# coffee_maker.net
KiCad netlist of a schematic drawn in EAGLE
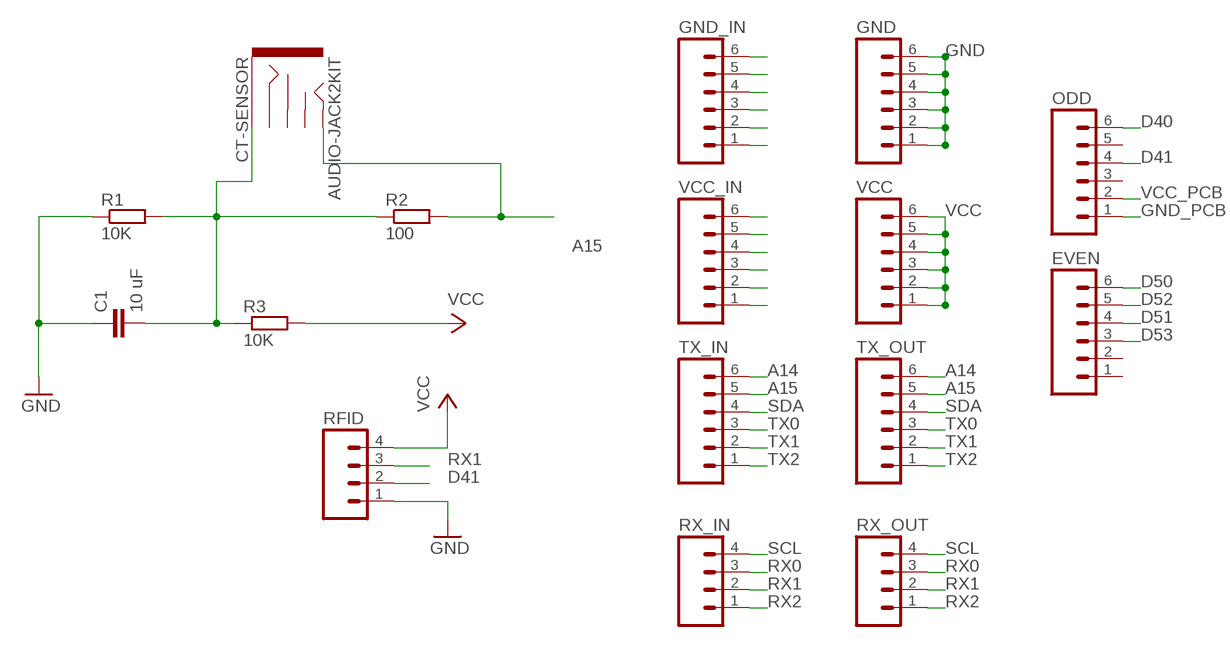
[diagram p0: schematic, sheet 1]

(export (version "E")
  (design (tool "Eeschema 10.0.6"))
  (components
    (comp (ref "C1")
      (value "10 uF")
      (footprint "eagle-import:C1206")
      (libsource (lib "eagle-import") (part "C-EUC1206"))
    )
    (comp (ref "CT-SENSOR")
      (value "AUDIO-JACK2KIT")
      (footprint "eagle-import:AUDIO-JACK-KIT")
      (libsource (lib "eagle-import") (part "AUDIO-JACK2KIT"))
    )
    (comp (ref "EVEN")
      (value "M06SIP")
      (footprint "eagle-import:1X06")
      (libsource (lib "eagle-import") (part "M06SIP"))
    )
    (comp (ref "GND")
      (value "M06SIP")
      (footprint "eagle-import:1X06")
      (libsource (lib "eagle-import") (part "M06SIP"))
    )
    (comp (ref "GND_IN")
      (value "M06SIP")
      (footprint "eagle-import:1X06")
      (libsource (lib "eagle-import") (part "M06SIP"))
    )
    (comp (ref "ODD")
      (value "M06SIP")
      (footprint "eagle-import:1X06")
      (libsource (lib "eagle-import") (part "M06SIP"))
    )
    (comp (ref "R1")
      (value "10K")
      (footprint "eagle-import:M1206")
      (libsource (lib "eagle-import") (part "R-EU_M1206"))
    )
    (comp (ref "R2")
      (value "100")
      (footprint "eagle-import:M1206")
      (libsource (lib "eagle-import") (part "R-EU_M1206"))
    )
    (comp (ref "R3")
      (value "10K")
      (footprint "eagle-import:M1206")
      (libsource (lib "eagle-import") (part "R-EU_M1206"))
    )
    (comp (ref "RFID")
      (value "M04SMD2")
      (footprint "eagle-import:1X04-1MM-RA")
      (libsource (lib "eagle-import") (part "M04SMD2"))
    )
    (comp (ref "RX_IN")
      (value "M04PTH")
      (footprint "eagle-import:1X04")
      (libsource (lib "eagle-import") (part "M04PTH"))
    )
    (comp (ref "RX_OUT")
      (value "M04PTH")
      (footprint "eagle-import:1X04")
      (libsource (lib "eagle-import") (part "M04PTH"))
    )
    (comp (ref "TX_IN")
      (value "M06SIP")
      (footprint "eagle-import:1X06")
      (libsource (lib "eagle-import") (part "M06SIP"))
    )
    (comp (ref "TX_OUT")
      (value "M06SIP")
      (footprint "eagle-import:1X06")
      (libsource (lib "eagle-import") (part "M06SIP"))
    )
    (comp (ref "VCC")
      (value "M06SIP")
      (footprint "eagle-import:1X06")
      (libsource (lib "eagle-import") (part "M06SIP"))
    )
    (comp (ref "VCC_IN")
      (value "M06SIP")
      (footprint "eagle-import:1X06")
      (libsource (lib "eagle-import") (part "M06SIP"))
    )
  )
  (nets
    (net (code "1") (name "/A14") (class "Default")
      (node (ref "TX_IN") (pin "6") (pinfunction "6_6") (pintype "passive"))
      (node (ref "TX_OUT") (pin "6") (pinfunction "6_6") (pintype "passive"))
    )
    (net (code "2") (name "/A15") (class "Default")
      (node (ref "CT-SENSOR") (pin "TIP") (pinfunction "TIP_TIP") (pintype "bidirectional"))
      (node (ref "R2") (pin "2") (pinfunction "2_2") (pintype "passive"))
      (node (ref "TX_IN") (pin "5") (pinfunction "5_5") (pintype "passive"))
      (node (ref "TX_OUT") (pin "5") (pinfunction "5_5") (pintype "passive"))
    )
    (net (code "3") (name "/D40") (class "Default")
      (node (ref "ODD") (pin "6") (pinfunction "6_6") (pintype "passive"))
    )
    (net (code "4") (name "/D41") (class "Default")
      (node (ref "ODD") (pin "4") (pinfunction "4_4") (pintype "passive"))
      (node (ref "RFID") (pin "2") (pinfunction "2_2") (pintype "passive"))
    )
    (net (code "5") (name "/D50") (class "Default")
      (node (ref "EVEN") (pin "6") (pinfunction "6_6") (pintype "passive"))
    )
    (net (code "6") (name "/D51") (class "Default")
      (node (ref "EVEN") (pin "4") (pinfunction "4_4") (pintype "passive"))
    )
    (net (code "7") (name "/D52") (class "Default")
      (node (ref "EVEN") (pin "5") (pinfunction "5_5") (pintype "passive"))
    )
    (net (code "8") (name "/D53") (class "Default")
      (node (ref "EVEN") (pin "3") (pinfunction "3_3") (pintype "passive"))
    )
    (net (code "9") (name "/GND_PCB") (class "Default")
      (node (ref "ODD") (pin "1") (pinfunction "1_1") (pintype "passive"))
    )
    (net (code "10") (name "/RX0") (class "Default")
      (node (ref "RX_IN") (pin "3") (pinfunction "3_3") (pintype "passive"))
      (node (ref "RX_OUT") (pin "3") (pinfunction "3_3") (pintype "passive"))
    )
    (net (code "11") (name "/RX1") (class "Default")
      (node (ref "RFID") (pin "3") (pinfunction "3_3") (pintype "passive"))
      (node (ref "RX_IN") (pin "2") (pinfunction "2_2") (pintype "passive"))
      (node (ref "RX_OUT") (pin "2") (pinfunction "2_2") (pintype "passive"))
    )
    (net (code "12") (name "/RX2") (class "Default")
      (node (ref "RX_IN") (pin "1") (pinfunction "1_1") (pintype "passive"))
      (node (ref "RX_OUT") (pin "1") (pinfunction "1_1") (pintype "passive"))
    )
    (net (code "13") (name "/SCL") (class "Default")
      (node (ref "RX_IN") (pin "4") (pinfunction "4_4") (pintype "passive"))
      (node (ref "RX_OUT") (pin "4") (pinfunction "4_4") (pintype "passive"))
    )
    (net (code "14") (name "/SDA") (class "Default")
      (node (ref "TX_IN") (pin "4") (pinfunction "4_4") (pintype "passive"))
      (node (ref "TX_OUT") (pin "4") (pinfunction "4_4") (pintype "passive"))
    )
    (net (code "15") (name "/TX0") (class "Default")
      (node (ref "TX_IN") (pin "3") (pinfunction "3_3") (pintype "passive"))
      (node (ref "TX_OUT") (pin "3") (pinfunction "3_3") (pintype "passive"))
    )
    (net (code "16") (name "/TX1") (class "Default")
      (node (ref "TX_IN") (pin "2") (pinfunction "2_2") (pintype "passive"))
      (node (ref "TX_OUT") (pin "2") (pinfunction "2_2") (pintype "passive"))
    )
    (net (code "17") (name "/TX2") (class "Default")
      (node (ref "TX_IN") (pin "1") (pinfunction "1_1") (pintype "passive"))
      (node (ref "TX_OUT") (pin "1") (pinfunction "1_1") (pintype "passive"))
    )
    (net (code "18") (name "/VCC_PCB") (class "Default")
      (node (ref "ODD") (pin "2") (pinfunction "2_2") (pintype "passive"))
    )
    (net (code "19") (name "GND") (class "Default")
      (node (ref "C1") (pin "1") (pinfunction "1_1") (pintype "passive"))
      (node (ref "GND") (pin "1") (pinfunction "1_1") (pintype "passive"))
      (node (ref "GND") (pin "2") (pinfunction "2_2") (pintype "passive"))
      (node (ref "GND") (pin "3") (pinfunction "3_3") (pintype "passive"))
      (node (ref "GND") (pin "4") (pinfunction "4_4") (pintype "passive"))
      (node (ref "GND") (pin "5") (pinfunction "5_5") (pintype "passive"))
      (node (ref "GND") (pin "6") (pinfunction "6_6") (pintype "passive"))
      (node (ref "GND_IN") (pin "6") (pinfunction "6_6") (pintype "passive"))
      (node (ref "R1") (pin "1") (pinfunction "1_1") (pintype "passive"))
      (node (ref "RFID") (pin "1") (pinfunction "1_1") (pintype "passive"))
    )
    (net (code "20") (name "Net-(C1-Pad2)") (class "Default")
      (node (ref "C1") (pin "2") (pinfunction "2_2") (pintype "passive"))
      (node (ref "CT-SENSOR") (pin "SLEEVE") (pinfunction "SLEEVE_SLEEVE") (pintype "bidirectional"))
      (node (ref "R1") (pin "2") (pinfunction "2_2") (pintype "passive"))
      (node (ref "R2") (pin "1") (pinfunction "1_1") (pintype "passive"))
      (node (ref "R3") (pin "1") (pinfunction "1_1") (pintype "passive"))
    )
    (net (code "21") (name "VCC") (class "Default")
      (node (ref "R3") (pin "2") (pinfunction "2_2") (pintype "passive"))
      (node (ref "RFID") (pin "4") (pinfunction "4_4") (pintype "passive"))
      (node (ref "VCC") (pin "1") (pinfunction "1_1") (pintype "passive"))
      (node (ref "VCC") (pin "2") (pinfunction "2_2") (pintype "passive"))
      (node (ref "VCC") (pin "3") (pinfunction "3_3") (pintype "passive"))
      (node (ref "VCC") (pin "4") (pinfunction "4_4") (pintype "passive"))
      (node (ref "VCC") (pin "5") (pinfunction "5_5") (pintype "passive"))
      (node (ref "VCC") (pin "6") (pinfunction "6_6") (pintype "passive"))
      (node (ref "VCC_IN") (pin "1") (pinfunction "1_1") (pintype "passive"))
    )
    (net (code "22") (name "unconnected-(CT-SENSOR-PadRING)") (class "Default")
      (node (ref "CT-SENSOR") (pin "RING") (pinfunction "RING_RING") (pintype "bidirectional"))
    )
    (net (code "23") (name "unconnected-(CT-SENSOR-PadRSH)") (class "Default")
      (node (ref "CT-SENSOR") (pin "RSH") (pinfunction "RSH_RSH") (pintype "bidirectional"))
    )
    (net (code "24") (name "unconnected-(CT-SENSOR-PadTSH)") (class "Default")
      (node (ref "CT-SENSOR") (pin "TSH") (pinfunction "TSH_TSH") (pintype "bidirectional"))
    )
    (net (code "25") (name "unconnected-(EVEN-Pad1)") (class "Default")
      (node (ref "EVEN") (pin "1") (pinfunction "1_1") (pintype "passive"))
    )
    (net (code "26") (name "unconnected-(EVEN-Pad2)") (class "Default")
      (node (ref "EVEN") (pin "2") (pinfunction "2_2") (pintype "passive"))
    )
    (net (code "27") (name "unconnected-(GND_IN-Pad1)") (class "Default")
      (node (ref "GND_IN") (pin "1") (pinfunction "1_1") (pintype "passive"))
    )
    (net (code "28") (name "unconnected-(GND_IN-Pad2)") (class "Default")
      (node (ref "GND_IN") (pin "2") (pinfunction "2_2") (pintype "passive"))
    )
    (net (code "29") (name "unconnected-(GND_IN-Pad3)") (class "Default")
      (node (ref "GND_IN") (pin "3") (pinfunction "3_3") (pintype "passive"))
    )
    (net (code "30") (name "unconnected-(GND_IN-Pad4)") (class "Default")
      (node (ref "GND_IN") (pin "4") (pinfunction "4_4") (pintype "passive"))
    )
    (net (code "31") (name "unconnected-(GND_IN-Pad5)") (class "Default")
      (node (ref "GND_IN") (pin "5") (pinfunction "5_5") (pintype "passive"))
    )
    (net (code "32") (name "unconnected-(ODD-Pad3)") (class "Default")
      (node (ref "ODD") (pin "3") (pinfunction "3_3") (pintype "passive"))
    )
    (net (code "33") (name "unconnected-(ODD-Pad5)") (class "Default")
      (node (ref "ODD") (pin "5") (pinfunction "5_5") (pintype "passive"))
    )
    (net (code "34") (name "unconnected-(VCC_IN-Pad2)") (class "Default")
      (node (ref "VCC_IN") (pin "2") (pinfunction "2_2") (pintype "passive"))
    )
    (net (code "35") (name "unconnected-(VCC_IN-Pad3)") (class "Default")
      (node (ref "VCC_IN") (pin "3") (pinfunction "3_3") (pintype "passive"))
    )
    (net (code "36") (name "unconnected-(VCC_IN-Pad4)") (class "Default")
      (node (ref "VCC_IN") (pin "4") (pinfunction "4_4") (pintype "passive"))
    )
    (net (code "37") (name "unconnected-(VCC_IN-Pad5)") (class "Default")
      (node (ref "VCC_IN") (pin "5") (pinfunction "5_5") (pintype "passive"))
    )
    (net (code "38") (name "unconnected-(VCC_IN-Pad6)") (class "Default")
      (node (ref "VCC_IN") (pin "6") (pinfunction "6_6") (pintype "passive"))
    )
  )
)
